# Sheet1.net
KiCad netlist of a schematic drawn in Altium Designer
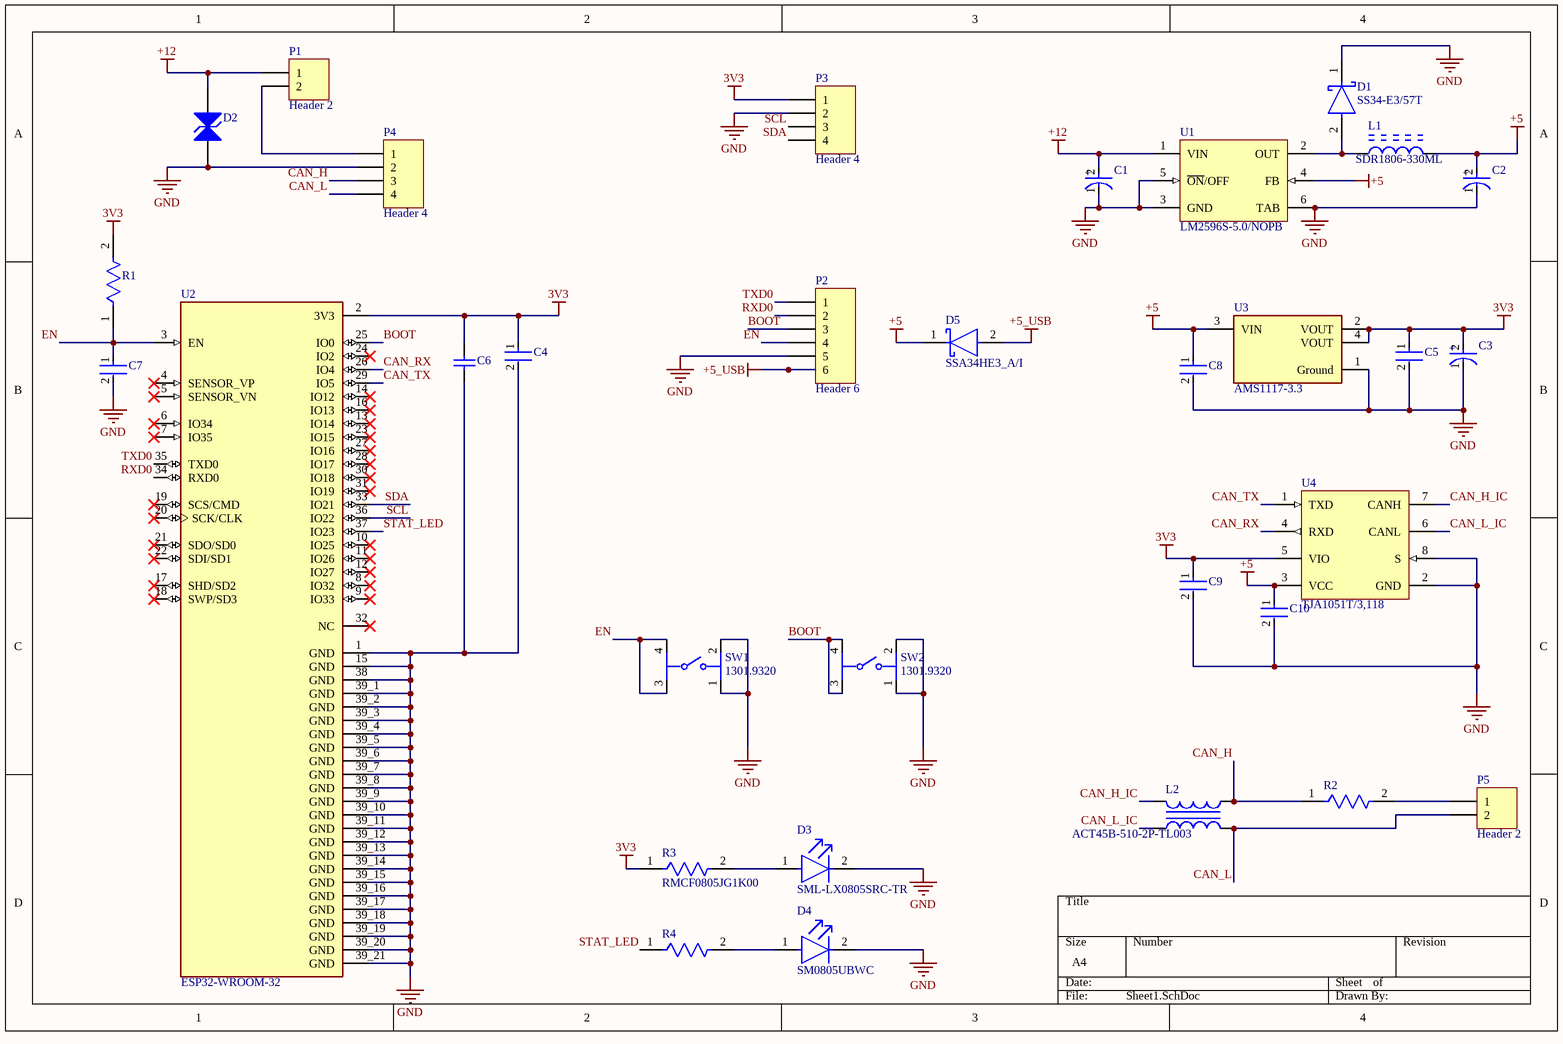
[diagram p0: Sheet1.SchDoc]

(export (version "E")
  (design (tool "Eeschema 10.0.6"))
  (components
    (comp (ref "C1")
      (value "EEE-TQV101XAP")
      (footprint "FP-TQD8-MFG")
      (description "CAP ALUM 100UF 20% 35V SMD")
      (fields (field (name "VOLTAGE") "35V") (field (name "TOLERANCE") "20%"))
      (libsource (lib "Altium Content Vault") (part "203bc49f2ac43e59fd269a8c329ed05"))
    )
    (comp (ref "C2")
      (value "EEE-TQV101XAP")
      (footprint "FP-TQD8-MFG")
      (description "CAP ALUM 100UF 20% 35V SMD")
      (fields (field (name "VOLTAGE") "35V") (field (name "TOLERANCE") "20%"))
      (libsource (lib "Altium Content Vault") (part "203bc49f2ac43e59fd269a8c329ed05"))
    )
    (comp (ref "C3")
      (value "EEE-TQV101XAP")
      (footprint "FP-TQD8-MFG")
      (description "CAP ALUM 100UF 20% 35V SMD")
      (fields (field (name "VOLTAGE") "35V") (field (name "TOLERANCE") "20%"))
      (libsource (lib "Altium Content Vault") (part "203bc49f2ac43e59fd269a8c329ed05"))
    )
    (comp (ref "C4")
      (value "GRM21BZ71C106KE15L")
      (footprint "FP-GRM21B-0_2-e0_2_0_7-IPC_C")
      (description "Chip Multilayer Ceramic Capacitors for General Purpose, 0805, 10uF, X7R, 15%, 10%, 16V")
      (libsource (lib "Altium Content Vault") (part "b4654b650e69147ec39a6b967a45e02"))
    )
    (comp (ref "C5")
      (value "GRM21BZ71C106KE15L")
      (footprint "FP-GRM21B-0_2-e0_2_0_7-IPC_C")
      (description "Chip Multilayer Ceramic Capacitors for General Purpose, 0805, 10uF, X7R, 15%, 10%, 16V")
      (libsource (lib "Altium Content Vault") (part "b4654b650e69147ec39a6b967a45e02"))
    )
    (comp (ref "C6")
      (value "C0805S104K5RACTU")
      (footprint "CAPC2013X145X50NL20T25")
      (fields (field (name "MANUFACTURER") "Kemet"))
      (libsource (lib "Altium Content Vault") (part "CAP"))
    )
    (comp (ref "C7")
      (value "GRM21BZ71C106KE15L")
      (footprint "FP-GRM21B-0_2-e0_2_0_7-IPC_C")
      (description "Chip Multilayer Ceramic Capacitors for General Purpose, 0805, 10uF, X7R, 15%, 10%, 16V")
      (libsource (lib "Altium Content Vault") (part "b4654b650e69147ec39a6b967a45e02"))
    )
    (comp (ref "C8")
      (value "GRM21BZ71C106KE15L")
      (footprint "FP-GRM21B-0_2-e0_2_0_7-IPC_C")
      (description "Chip Multilayer Ceramic Capacitors for General Purpose, 0805, 10uF, X7R, 15%, 10%, 16V")
      (libsource (lib "Altium Content Vault") (part "b4654b650e69147ec39a6b967a45e02"))
    )
    (comp (ref "C9")
      (value "GRM21BZ71C106KE15L")
      (footprint "FP-GRM21B-0_2-e0_2_0_7-IPC_C")
      (description "Chip Multilayer Ceramic Capacitors for General Purpose, 0805, 10uF, X7R, 15%, 10%, 16V")
      (libsource (lib "Altium Content Vault") (part "b4654b650e69147ec39a6b967a45e02"))
    )
    (comp (ref "C10")
      (value "GRM21BZ71C106KE15L")
      (footprint "FP-GRM21B-0_2-e0_2_0_7-IPC_C")
      (description "Chip Multilayer Ceramic Capacitors for General Purpose, 0805, 10uF, X7R, 15%, 10%, 16V")
      (libsource (lib "Altium Content Vault") (part "b4654b650e69147ec39a6b967a45e02"))
    )
    (comp (ref "D1")
      (value "SS34-E3/57T")
      (footprint "FP-95402-MFG")
      (description "DIODE SCHOTTKY 40V 3A DO214AB")
      (fields
        (field (name "MANUFACTURER") "Vishay")
        (field (name "OCTOPART") "https://octopart.com/ss34-e3%2F57t-vishay-39552907")
      )
      (libsource (lib "Altium Content Vault") (part "1d6ec82d83fb6aee721767c19dac4b9"))
    )
    (comp (ref "D2")
      (value "SMAJ15CA-E3/5A")
      (footprint "VISH-DO-214AC-2_M")
      (fields (field (name "MANUFACTURER") "Vishay Semiconductor"))
      (libsource (lib "Altium Content Vault") (part "VISH-A1A2-2"))
    )
    (comp (ref "D3")
      (value "SML-LX0805SRC-TR")
      (footprint "FP-SML-LX0805SRC-TR-MFG")
      (description "LED RED CLEAR SMD")
      (libsource (lib "Altium Content Vault") (part "ab1c01a81903e929fc6c44469aada92"))
    )
    (comp (ref "D4")
      (value "SM0805UBWC")
      (footprint "FP-SM0805UBWC-MFG")
      (description "LED BLUE CLEAR 0805 SMD")
      (libsource (lib "Altium Content Vault") (part "ab1c01a81903e929fc6c44469aada92"))
    )
    (comp (ref "D5")
      (value "SSA34HE3_A/I")
      (footprint "FP-95400-MFG")
      (description "DIODE SCHOTTKY 40V 3A DO214AC")
      (libsource (lib "Altium Content Vault") (part "1d6ec82d83fb6aee721767c19dac4b9"))
    )
    (comp (ref "L1")
      (value "SDR1806-330ML")
      (footprint "BOUR-SDR1806_V")
      (description "Power Inductor, 33 uH, +/- 20%, -40 to 125 degC, 2-Pin SMD, RoHS, Tape and Reel")
      (fields (field (name "MANUFACTURER") "Bourns") (field (name "TOLERANCE") "20%"))
      (libsource (lib "Altium Content Vault") (part "IND-FERR-2"))
    )
    (comp (ref "L2")
      (value "ACT45B-510-2P-TL003")
      (footprint "TDK-ACT45B-510-2P-TL003-4_V")
      (fields (field (name "MANUFACTURER") "TDK"))
      (libsource (lib "Altium Content Vault") (part "TDK-ACXXXXX-XXX-2P-T000-4"))
    )
    (comp (ref "P1")
      (value "Header 2")
      (footprint "HDR1X2")
      (description "Header, 2-Pin")
      (fields (field (name "PUBLISHER") "Altium Limited"))
      (libsource (lib "Miscellaneous Connectors") (part "Header 2"))
    )
    (comp (ref "P2")
      (value "Header 6")
      (footprint "HDR1X6")
      (description "Header, 6-Pin")
      (fields (field (name "PUBLISHER") "Altium Limited"))
      (libsource (lib "Miscellaneous Connectors") (part "Header 6"))
    )
    (comp (ref "P3")
      (value "Header 4")
      (footprint "HDR1X4")
      (description "Header, 4-Pin")
      (fields (field (name "PUBLISHER") "Altium Limited"))
      (libsource (lib "Miscellaneous Connectors") (part "Header 4"))
    )
    (comp (ref "P4")
      (value "Header 4")
      (footprint "HDR1X4")
      (description "Header, 4-Pin")
      (fields (field (name "PUBLISHER") "Altium Limited"))
      (libsource (lib "Miscellaneous Connectors") (part "Header 4"))
    )
    (comp (ref "P5")
      (value "Header 2")
      (footprint "HDR1X2")
      (description "Header, 2-Pin")
      (fields (field (name "PUBLISHER") "Altium Limited"))
      (libsource (lib "Miscellaneous Connectors") (part "Header 2"))
    )
    (comp (ref "R1")
      (value "CRGCQ0805J10K")
      (footprint "FP-CRGCQ0805-IPC_C")
      (description "CRGCQ 0805 10K 5%")
      (fields (field (name "MANUFACTURER") "TE Connectivity") (field (name "TOLERANCE") "0.05"))
      (libsource (lib "Altium Content Vault") (part "1029c3af85768c4190bb7ad29bc67b5"))
    )
    (comp (ref "R2")
      (value "AC0805FR-07120RL")
      (footprint "FP-AC0805-MFG")
      (description "RES SMD 120 OHM 1% 1/8W 0805")
      (fields
        (field (name "MANUFACTURER") "Yageo")
        (field (name "OCTOPART") "https://octopart.com/ac0805fr-07120rl-yageo-30510890")
      )
      (libsource (lib "Altium Content Vault") (part "1029c3af85768c4190bb7ad29bc67b5"))
    )
    (comp (ref "R3")
      (value "RMCF0805JG1K00")
      (footprint "FP-RMCF0805-IPC_B")
      (description "1kΩ ±5% 0.125W 0805 Thick Film Chip Resistor AEC-Q200 compliant")
      (fields (field (name "TOLERANCE") "5%"))
      (libsource (lib "Altium Content Vault") (part "1029c3af85768c4190bb7ad29bc67b5"))
    )
    (comp (ref "R4")
      (value "AC0805FR-07120RL")
      (footprint "FP-AC0805-MFG")
      (description "RES SMD 120 OHM 1% 1/8W 0805")
      (fields
        (field (name "MANUFACTURER") "Yageo")
        (field (name "OCTOPART") "https://octopart.com/ac0805fr-07120rl-yageo-30510890")
      )
      (libsource (lib "Altium Content Vault") (part "1029c3af85768c4190bb7ad29bc67b5"))
    )
    (comp (ref "SW1")
      (value "1301.9320")
      (footprint "FP-1301_9320-MFG")
      (description "SWITCH TACTILE SPST-NO 0.05A 12V")
      (fields
        (field (name "MANUFACTURER") "Schurter")
        (field (name "OCTOPART") "https://octopart.com/1301.9320-schurter-6627962")
      )
      (libsource (lib "Altium Content Vault") (part "c0df99d12937e9d2da15afdedf14b17"))
    )
    (comp (ref "SW2")
      (value "1301.9320")
      (footprint "FP-1301_9320-MFG")
      (description "SWITCH TACTILE SPST-NO 0.05A 12V")
      (fields
        (field (name "MANUFACTURER") "Schurter")
        (field (name "OCTOPART") "https://octopart.com/1301.9320-schurter-6627962")
      )
      (libsource (lib "Altium Content Vault") (part "c0df99d12937e9d2da15afdedf14b17"))
    )
    (comp (ref "U1")
      (value "LM2596S-5.0/NOPB")
      (footprint "KTT0005B_M")
      (description "SIMPLE SWITCHER® Power Converter 150 KHz 3A Step-Down Voltage Regulator, 5-pin TO-263, Pb-Free")
      (fields (field (name "MANUFACTURER") "Texas Instruments"))
      (libsource (lib "Altium Content Vault") (part "PM-REG-LM2575HVS-12"))
    )
    (comp (ref "U2")
      (value "ESP32-WROOM-32")
      (footprint "MODULE_ESP32-WROOM-32")
      (fields (field (name "MF") "Espressif Systems"))
      (libsource (lib "ESP32-WROOM-32") (part "ESP32-WROOM-32"))
    )
    (comp (ref "U3")
      (value "AMS1117-3.3")
      (footprint "FP-AMS1117-IPC_C")
      (description "LDO Voltage Regulators 1A, 3.3V")
      (fields
        (field (name "OCTOPART") "https://octopart.com/ams1117-3.3-advanced+monolithic+systems-25899300")
        (field (name "MANUFACTURER") "Advanced Monolithic Systems")
      )
      (libsource (lib "Altium Content Vault") (part "8bdbb5f8e77002000e30dd2845d0354"))
    )
    (comp (ref "U4")
      (value "TJA1051T/3,118")
      (footprint "NXP-SOIC-8_L")
      (description "High-Speed CAN Transceiver, 3 to 5 V, 8-Pin SOIC (SOT96-1), RoHS, Tape and Reel")
      (fields (field (name "MANUFACTURER") "NXP"))
      (libsource (lib "Altium Content Vault") (part "NXP-TJA1051T_3-SOIC-8"))
    )
  )
  (nets
    (net (code "1") (name "+5") (class "Default")
      (node (ref "C10") (pin "1") (pinfunction "1_1") (pintype "passive"))
      (node (ref "C2") (pin "2") (pinfunction "A_2") (pintype "passive"))
      (node (ref "C8") (pin "1") (pinfunction "1_1") (pintype "passive"))
      (node (ref "D5") (pin "1") (pinfunction "C_1") (pintype "passive"))
      (node (ref "L1") (pin "2") (pinfunction "2_2") (pintype "passive"))
      (node (ref "U1") (pin "4") (pinfunction "FB_4") (pintype "input"))
      (node (ref "U3") (pin "3") (pinfunction "VIN_3") (pintype "power_in"))
      (node (ref "U4") (pin "3") (pinfunction "VCC_3") (pintype "power_in"))
    )
    (net (code "2") (name "+5_USB") (class "Default")
      (node (ref "D5") (pin "2") (pinfunction "A_2") (pintype "passive"))
      (node (ref "P2") (pin "6") (pinfunction "6_6") (pintype "passive"))
    )
    (net (code "3") (name "+12") (class "Default")
      (node (ref "C1") (pin "2") (pinfunction "A_2") (pintype "passive"))
      (node (ref "D2") (pin "2") (pinfunction "A2_2") (pintype "passive"))
      (node (ref "P1") (pin "1") (pinfunction "1_1") (pintype "passive"))
      (node (ref "U1") (pin "1") (pinfunction "VIN_1") (pintype "power_in"))
    )
    (net (code "4") (name "/BOOT") (class "Default")
      (node (ref "P2") (pin "3") (pinfunction "3_3") (pintype "passive"))
      (node (ref "SW2") (pin "3") (pinfunction "3_3") (pintype "passive"))
      (node (ref "SW2") (pin "4") (pinfunction "4_4") (pintype "passive"))
      (node (ref "U2") (pin "25") (pinfunction "IO0_25") (pintype "bidirectional"))
    )
    (net (code "5") (name "/CAN_H") (class "Default")
      (node (ref "L2") (pin "4") (pinfunction "4_4") (pintype "passive"))
      (node (ref "P4") (pin "3") (pinfunction "3_3") (pintype "passive"))
      (node (ref "R2") (pin "1") (pinfunction "1_1") (pintype "passive"))
    )
    (net (code "6") (name "/CAN_H_IC") (class "Default")
      (node (ref "L2") (pin "1") (pinfunction "1_1") (pintype "passive"))
      (node (ref "U4") (pin "7") (pinfunction "CANH_7") (pintype "passive"))
    )
    (net (code "7") (name "/CAN_L") (class "Default")
      (node (ref "L2") (pin "3") (pinfunction "3_3") (pintype "passive"))
      (node (ref "P4") (pin "4") (pinfunction "4_4") (pintype "passive"))
      (node (ref "P5") (pin "2") (pinfunction "2_2") (pintype "passive"))
    )
    (net (code "8") (name "/CAN_L_IC") (class "Default")
      (node (ref "L2") (pin "2") (pinfunction "2_2") (pintype "passive"))
      (node (ref "U4") (pin "6") (pinfunction "CANL_6") (pintype "passive"))
    )
    (net (code "9") (name "/CAN_RX") (class "Default")
      (node (ref "U2") (pin "26") (pinfunction "IO4_26") (pintype "bidirectional"))
      (node (ref "U4") (pin "4") (pinfunction "RXD_4") (pintype "output"))
    )
    (net (code "10") (name "/CAN_TX") (class "Default")
      (node (ref "U2") (pin "29") (pinfunction "IO5_29") (pintype "bidirectional"))
      (node (ref "U4") (pin "1") (pinfunction "TXD_1") (pintype "input"))
    )
    (net (code "11") (name "/EN") (class "Default")
      (node (ref "C7") (pin "1") (pinfunction "1_1") (pintype "passive"))
      (node (ref "P2") (pin "4") (pinfunction "4_4") (pintype "passive"))
      (node (ref "R1") (pin "1") (pinfunction "1_1") (pintype "passive"))
      (node (ref "SW1") (pin "3") (pinfunction "3_3") (pintype "passive"))
      (node (ref "SW1") (pin "4") (pinfunction "4_4") (pintype "passive"))
      (node (ref "U2") (pin "3") (pinfunction "EN_3") (pintype "input"))
    )
    (net (code "12") (name "/RXD0") (class "Default")
      (node (ref "P2") (pin "2") (pinfunction "2_2") (pintype "passive"))
      (node (ref "U2") (pin "34") (pinfunction "RXD0_34") (pintype "bidirectional"))
    )
    (net (code "13") (name "/SCL") (class "Default")
      (node (ref "P3") (pin "3") (pinfunction "3_3") (pintype "passive"))
      (node (ref "U2") (pin "36") (pinfunction "IO22_36") (pintype "bidirectional"))
    )
    (net (code "14") (name "/SDA") (class "Default")
      (node (ref "P3") (pin "4") (pinfunction "4_4") (pintype "passive"))
      (node (ref "U2") (pin "33") (pinfunction "IO21_33") (pintype "bidirectional"))
    )
    (net (code "15") (name "/STAT_LED") (class "Default")
      (node (ref "R4") (pin "1") (pinfunction "1_1") (pintype "passive"))
      (node (ref "U2") (pin "37") (pinfunction "IO23_37") (pintype "bidirectional"))
    )
    (net (code "16") (name "/TXD0") (class "Default")
      (node (ref "P2") (pin "1") (pinfunction "1_1") (pintype "passive"))
      (node (ref "U2") (pin "35") (pinfunction "TXD0_35") (pintype "bidirectional"))
    )
    (net (code "17") (name "3V3") (class "Default")
      (node (ref "C3") (pin "2") (pinfunction "A_2") (pintype "passive"))
      (node (ref "C4") (pin "1") (pinfunction "1_1") (pintype "passive"))
      (node (ref "C5") (pin "1") (pinfunction "1_1") (pintype "passive"))
      (node (ref "C6") (pin "2") (pinfunction "2_2") (pintype "passive"))
      (node (ref "C9") (pin "1") (pinfunction "1_1") (pintype "passive"))
      (node (ref "P3") (pin "1") (pinfunction "1_1") (pintype "passive"))
      (node (ref "R1") (pin "2") (pinfunction "2_2") (pintype "passive"))
      (node (ref "R3") (pin "1") (pinfunction "1_1") (pintype "passive"))
      (node (ref "U2") (pin "2") (pinfunction "3V3_2") (pintype "power_in"))
      (node (ref "U3") (pin "2") (pinfunction "VOUT_2") (pintype "passive"))
      (node (ref "U3") (pin "4") (pinfunction "VOUT_4") (pintype "passive"))
      (node (ref "U4") (pin "5") (pinfunction "VIO_5") (pintype "power_in"))
    )
    (net (code "18") (name "GND") (class "Default")
      (node (ref "C1") (pin "1") (pinfunction "C_1") (pintype "passive"))
      (node (ref "C10") (pin "2") (pinfunction "2_2") (pintype "passive"))
      (node (ref "C2") (pin "1") (pinfunction "C_1") (pintype "passive"))
      (node (ref "C3") (pin "1") (pinfunction "C_1") (pintype "passive"))
      (node (ref "C4") (pin "2") (pinfunction "2_2") (pintype "passive"))
      (node (ref "C5") (pin "2") (pinfunction "2_2") (pintype "passive"))
      (node (ref "C6") (pin "1") (pinfunction "1_1") (pintype "passive"))
      (node (ref "C7") (pin "2") (pinfunction "2_2") (pintype "passive"))
      (node (ref "C8") (pin "2") (pinfunction "2_2") (pintype "passive"))
      (node (ref "C9") (pin "2") (pinfunction "2_2") (pintype "passive"))
      (node (ref "D1") (pin "1") (pinfunction "C_1") (pintype "passive"))
      (node (ref "D2") (pin "1") (pinfunction "A1_1") (pintype "passive"))
      (node (ref "D3") (pin "2") (pinfunction "C_2") (pintype "passive"))
      (node (ref "D4") (pin "2") (pinfunction "C_2") (pintype "passive"))
      (node (ref "P2") (pin "5") (pinfunction "5_5") (pintype "passive"))
      (node (ref "P3") (pin "2") (pinfunction "2_2") (pintype "passive"))
      (node (ref "P4") (pin "2") (pinfunction "2_2") (pintype "passive"))
      (node (ref "SW1") (pin "1") (pinfunction "1_1") (pintype "passive"))
      (node (ref "SW1") (pin "2") (pinfunction "2_2") (pintype "passive"))
      (node (ref "SW2") (pin "1") (pinfunction "1_1") (pintype "passive"))
      (node (ref "SW2") (pin "2") (pinfunction "2_2") (pintype "passive"))
      (node (ref "U1") (pin "3") (pinfunction "GND_3") (pintype "power_in"))
      (node (ref "U1") (pin "5") (pinfunction "~{ON}/OFF_5") (pintype "input"))
      (node (ref "U1") (pin "6") (pinfunction "TAB_6") (pintype "power_in"))
      (node (ref "U2") (pin "1") (pinfunction "GND_1") (pintype "power_in"))
      (node (ref "U2") (pin "15") (pinfunction "GND_15") (pintype "power_in"))
      (node (ref "U2") (pin "38") (pinfunction "GND_38") (pintype "power_in"))
      (node (ref "U2") (pin "39_1") (pinfunction "GND_39_1") (pintype "power_in"))
      (node (ref "U2") (pin "39_10") (pinfunction "GND_39_10") (pintype "power_in"))
      (node (ref "U2") (pin "39_11") (pinfunction "GND_39_11") (pintype "power_in"))
      (node (ref "U2") (pin "39_12") (pinfunction "GND_39_12") (pintype "power_in"))
      (node (ref "U2") (pin "39_13") (pinfunction "GND_39_13") (pintype "power_in"))
      (node (ref "U2") (pin "39_14") (pinfunction "GND_39_14") (pintype "power_in"))
      (node (ref "U2") (pin "39_15") (pinfunction "GND_39_15") (pintype "power_in"))
      (node (ref "U2") (pin "39_16") (pinfunction "GND_39_16") (pintype "power_in"))
      (node (ref "U2") (pin "39_17") (pinfunction "GND_39_17") (pintype "power_in"))
      (node (ref "U2") (pin "39_18") (pinfunction "GND_39_18") (pintype "power_in"))
      (node (ref "U2") (pin "39_19") (pinfunction "GND_39_19") (pintype "power_in"))
      (node (ref "U2") (pin "39_2") (pinfunction "GND_39_2") (pintype "power_in"))
      (node (ref "U2") (pin "39_20") (pinfunction "GND_39_20") (pintype "power_in"))
      (node (ref "U2") (pin "39_21") (pinfunction "GND_39_21") (pintype "power_in"))
      (node (ref "U2") (pin "39_3") (pinfunction "GND_39_3") (pintype "power_in"))
      (node (ref "U2") (pin "39_4") (pinfunction "GND_39_4") (pintype "power_in"))
      (node (ref "U2") (pin "39_5") (pinfunction "GND_39_5") (pintype "power_in"))
      (node (ref "U2") (pin "39_6") (pinfunction "GND_39_6") (pintype "power_in"))
      (node (ref "U2") (pin "39_7") (pinfunction "GND_39_7") (pintype "power_in"))
      (node (ref "U2") (pin "39_8") (pinfunction "GND_39_8") (pintype "power_in"))
      (node (ref "U2") (pin "39_9") (pinfunction "GND_39_9") (pintype "power_in"))
      (node (ref "U3") (pin "1") (pinfunction "Ground_1") (pintype "power_in"))
      (node (ref "U4") (pin "2") (pinfunction "GND_2") (pintype "power_in"))
      (node (ref "U4") (pin "8") (pinfunction "S_8") (pintype "input"))
    )
    (net (code "19") (name "Net-(D1-A)") (class "Default")
      (node (ref "D1") (pin "2") (pinfunction "A_2") (pintype "passive"))
      (node (ref "L1") (pin "1") (pinfunction "1_1") (pintype "passive"))
      (node (ref "U1") (pin "2") (pinfunction "OUT_2") (pintype "power_in"))
    )
    (net (code "20") (name "Net-(D3-A)") (class "Default")
      (node (ref "D3") (pin "1") (pinfunction "A_1") (pintype "passive"))
      (node (ref "R3") (pin "2") (pinfunction "2_2") (pintype "passive"))
    )
    (net (code "21") (name "Net-(D4-A)") (class "Default")
      (node (ref "D4") (pin "1") (pinfunction "A_1") (pintype "passive"))
      (node (ref "R4") (pin "2") (pinfunction "2_2") (pintype "passive"))
    )
    (net (code "22") (name "Net-(P1-Pad2)") (class "Default")
      (node (ref "P1") (pin "2") (pinfunction "2_2") (pintype "passive"))
      (node (ref "P4") (pin "1") (pinfunction "1_1") (pintype "passive"))
    )
    (net (code "23") (name "Net-(P5-Pad1)") (class "Default")
      (node (ref "P5") (pin "1") (pinfunction "1_1") (pintype "passive"))
      (node (ref "R2") (pin "2") (pinfunction "2_2") (pintype "passive"))
    )
    (net (code "24") (name "unconnected-(U2-IO2-Pad24)") (class "Default")
      (node (ref "U2") (pin "24") (pinfunction "IO2_24") (pintype "bidirectional+no_connect"))
    )
    (net (code "25") (name "unconnected-(U2-IO12-Pad14)") (class "Default")
      (node (ref "U2") (pin "14") (pinfunction "IO12_14") (pintype "bidirectional+no_connect"))
    )
    (net (code "26") (name "unconnected-(U2-IO13-Pad16)") (class "Default")
      (node (ref "U2") (pin "16") (pinfunction "IO13_16") (pintype "bidirectional+no_connect"))
    )
    (net (code "27") (name "unconnected-(U2-IO14-Pad13)") (class "Default")
      (node (ref "U2") (pin "13") (pinfunction "IO14_13") (pintype "bidirectional+no_connect"))
    )
    (net (code "28") (name "unconnected-(U2-IO15-Pad23)") (class "Default")
      (node (ref "U2") (pin "23") (pinfunction "IO15_23") (pintype "bidirectional+no_connect"))
    )
    (net (code "29") (name "unconnected-(U2-IO16-Pad27)") (class "Default")
      (node (ref "U2") (pin "27") (pinfunction "IO16_27") (pintype "bidirectional+no_connect"))
    )
    (net (code "30") (name "unconnected-(U2-IO17-Pad28)") (class "Default")
      (node (ref "U2") (pin "28") (pinfunction "IO17_28") (pintype "bidirectional+no_connect"))
    )
    (net (code "31") (name "unconnected-(U2-IO18-Pad30)") (class "Default")
      (node (ref "U2") (pin "30") (pinfunction "IO18_30") (pintype "bidirectional+no_connect"))
    )
    (net (code "32") (name "unconnected-(U2-IO19-Pad31)") (class "Default")
      (node (ref "U2") (pin "31") (pinfunction "IO19_31") (pintype "bidirectional+no_connect"))
    )
    (net (code "33") (name "unconnected-(U2-IO25-Pad10)") (class "Default")
      (node (ref "U2") (pin "10") (pinfunction "IO25_10") (pintype "bidirectional+no_connect"))
    )
    (net (code "34") (name "unconnected-(U2-IO26-Pad11)") (class "Default")
      (node (ref "U2") (pin "11") (pinfunction "IO26_11") (pintype "bidirectional+no_connect"))
    )
    (net (code "35") (name "unconnected-(U2-IO27-Pad12)") (class "Default")
      (node (ref "U2") (pin "12") (pinfunction "IO27_12") (pintype "bidirectional+no_connect"))
    )
    (net (code "36") (name "unconnected-(U2-IO32-Pad8)") (class "Default")
      (node (ref "U2") (pin "8") (pinfunction "IO32_8") (pintype "bidirectional+no_connect"))
    )
    (net (code "37") (name "unconnected-(U2-IO33-Pad9)") (class "Default")
      (node (ref "U2") (pin "9") (pinfunction "IO33_9") (pintype "bidirectional+no_connect"))
    )
    (net (code "38") (name "unconnected-(U2-IO34-Pad6)") (class "Default")
      (node (ref "U2") (pin "6") (pinfunction "IO34_6") (pintype "input+no_connect"))
    )
    (net (code "39") (name "unconnected-(U2-IO35-Pad7)") (class "Default")
      (node (ref "U2") (pin "7") (pinfunction "IO35_7") (pintype "input+no_connect"))
    )
    (net (code "40") (name "unconnected-(U2-NC-Pad32)") (class "Default")
      (node (ref "U2") (pin "32") (pinfunction "NC_32") (pintype "passive+no_connect"))
    )
    (net (code "41") (name "unconnected-(U2-SCK{slash}CLK-Pad20)") (class "Default")
      (node (ref "U2") (pin "20") (pinfunction "SCK/CLK_20") (pintype "bidirectional+no_connect"))
    )
    (net (code "42") (name "unconnected-(U2-SCS{slash}CMD-Pad19)") (class "Default")
      (node (ref "U2") (pin "19") (pinfunction "SCS/CMD_19") (pintype "bidirectional+no_connect"))
    )
    (net (code "43") (name "unconnected-(U2-SDI{slash}SD1-Pad22)") (class "Default")
      (node (ref "U2") (pin "22") (pinfunction "SDI/SD1_22") (pintype "bidirectional+no_connect"))
    )
    (net (code "44") (name "unconnected-(U2-SDO{slash}SD0-Pad21)") (class "Default")
      (node (ref "U2") (pin "21") (pinfunction "SDO/SD0_21") (pintype "bidirectional+no_connect"))
    )
    (net (code "45") (name "unconnected-(U2-SENSOR_VN-Pad5)") (class "Default")
      (node (ref "U2") (pin "5") (pinfunction "SENSOR_VN_5") (pintype "input+no_connect"))
    )
    (net (code "46") (name "unconnected-(U2-SENSOR_VP-Pad4)") (class "Default")
      (node (ref "U2") (pin "4") (pinfunction "SENSOR_VP_4") (pintype "input+no_connect"))
    )
    (net (code "47") (name "unconnected-(U2-SHD{slash}SD2-Pad17)") (class "Default")
      (node (ref "U2") (pin "17") (pinfunction "SHD/SD2_17") (pintype "bidirectional+no_connect"))
    )
    (net (code "48") (name "unconnected-(U2-SWP{slash}SD3-Pad18)") (class "Default")
      (node (ref "U2") (pin "18") (pinfunction "SWP/SD3_18") (pintype "bidirectional+no_connect"))
    )
  )
)
